# adc_filter.net
KiCad netlist of a schematic drawn in Altium Designer
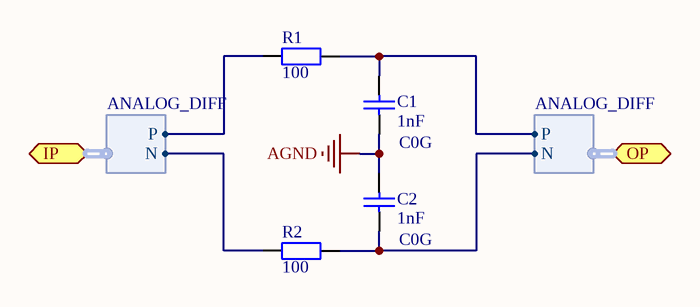
[diagram p0: adc filter.SchDoc]

(export (version "E")
  (design (tool "Eeschema 10.0.6"))
  (components
    (comp (ref "C1")
      (value "1nF")
      (footprint "C0603")
      (description "Capacitor")
      (fields
        (field (name "TYPE") "C0G")
        (field (name "Comment") "Cap")
        (field (name "PUBLISHER") "Altium Limited")
      )
      (libsource (lib "Miscellaneous Devices") (part "Cap"))
    )
    (comp (ref "C2")
      (value "1nF")
      (footprint "C0603")
      (description "Capacitor")
      (fields
        (field (name "TYPE") "C0G")
        (field (name "Comment") "Cap")
        (field (name "PUBLISHER") "Altium Limited")
      )
      (libsource (lib "Miscellaneous Devices") (part "Cap"))
    )
    (comp (ref "R1")
      (value "100")
      (footprint "R0603")
      (description "Resistor")
      (fields (field (name "Comment") "Res2") (field (name "PUBLISHER") "Altium Limited"))
      (libsource (lib "Miscellaneous Devices") (part "Res2"))
    )
    (comp (ref "R2")
      (value "100")
      (footprint "R0603")
      (description "Resistor")
      (fields (field (name "Comment") "Res2") (field (name "PUBLISHER") "Altium Limited"))
      (libsource (lib "Miscellaneous Devices") (part "Res2"))
    )
  )
  (nets
    (net (code "3") (name "AGND") (class "Default")
      (node (ref "C1") (pin "1") (pinfunction "1_1") (pintype "passive"))
      (node (ref "C2") (pin "2") (pinfunction "2_2") (pintype "passive"))
    )
    (net (code "4") (name "Net-(C1-Pad2)") (class "Default")
      (node (ref "C1") (pin "2") (pinfunction "2_2") (pintype "passive"))
      (node (ref "R1") (pin "2") (pinfunction "2_2") (pintype "passive"))
    )
    (net (code "5") (name "Net-(C2-Pad1)") (class "Default")
      (node (ref "C2") (pin "1") (pinfunction "1_1") (pintype "passive"))
      (node (ref "R2") (pin "2") (pinfunction "2_2") (pintype "passive"))
    )
    (net (code "6") (name "unconnected-(R1-Pad1)") (class "Default")
      (node (ref "R1") (pin "1") (pinfunction "1_1") (pintype "passive"))
    )
    (net (code "7") (name "unconnected-(R2-Pad1)") (class "Default")
      (node (ref "R2") (pin "1") (pinfunction "1_1") (pintype "passive"))
    )
  )
)
